# Power_Supply.net
KiCad netlist of a schematic drawn in Altium Designer
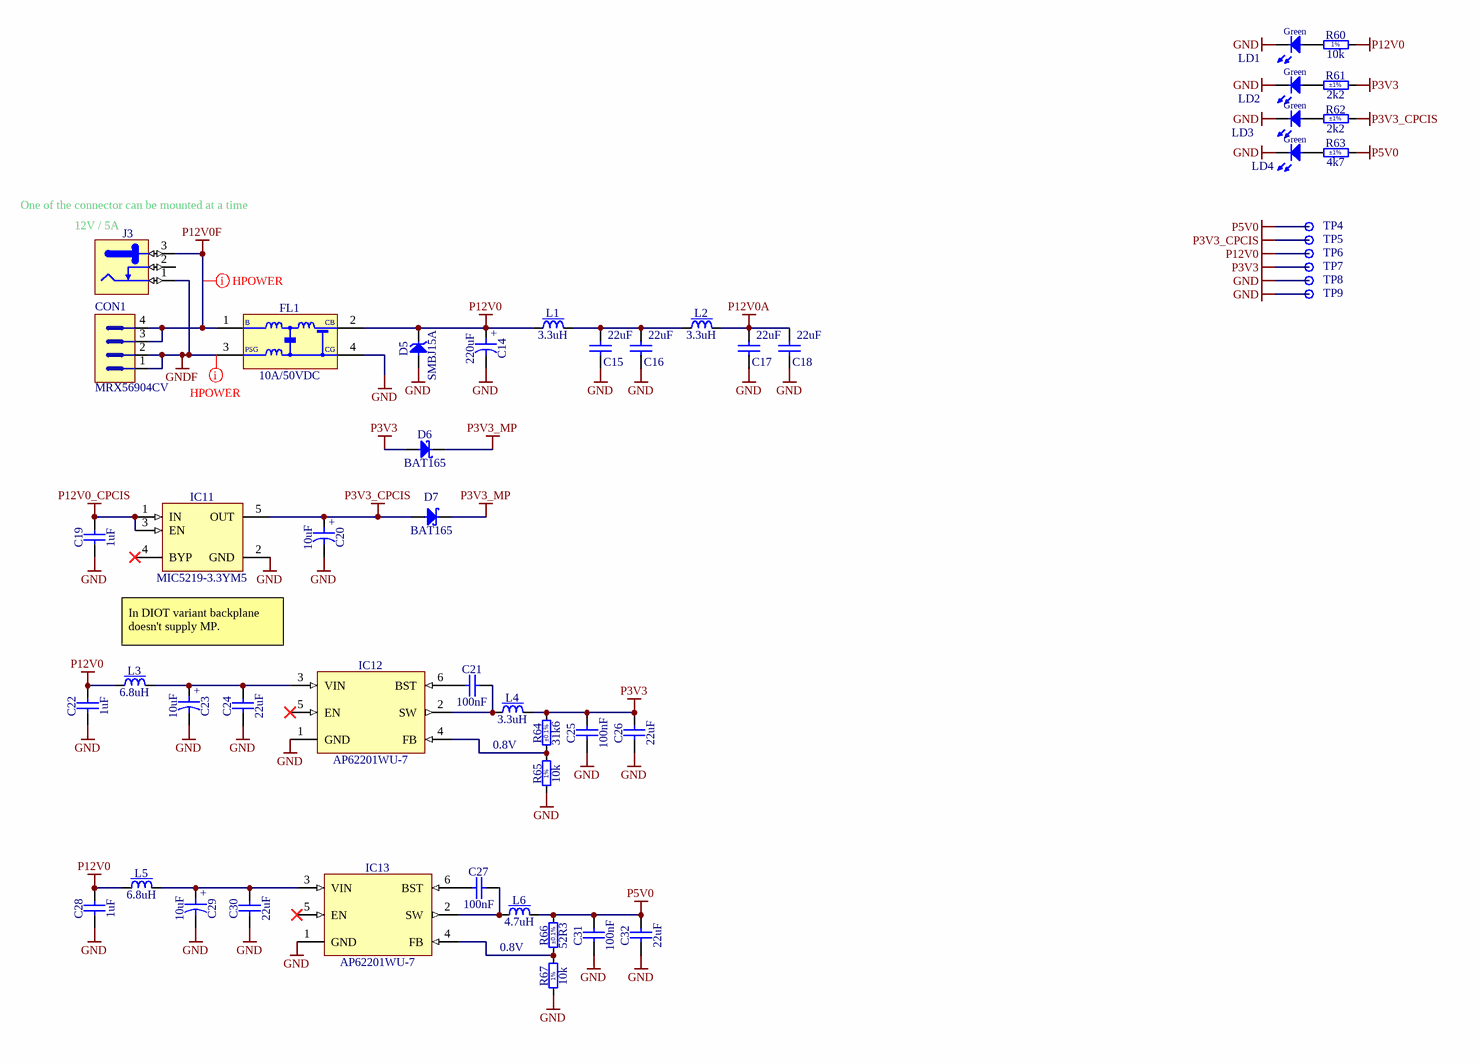
[diagram p0: Power_Supply.SchDoc]

(export (version "E")
  (design (tool "Eeschema 10.0.6"))
  (components
    (comp (ref "C14")
      (value "220uF")
      (footprint "CAPAE830X620N")
      (description "Polarised capacitor")
      (fields
        (field (name "PART NUMBER") "CAE830-620_220UF_16V_20%")
        (field (name "VOLTAGE") "16V")
        (field (name "AUTHOR") "CERN DEM JLC")
      )
      (libsource (lib "Capacitors") (part "Capacitor - polarized"))
    )
    (comp (ref "C15")
      (value "22uF")
      (footprint "CAPC2012X135N")
      (description "Non-polarised capacitor")
      (fields
        (field (name "PART NUMBER") "CC0805_22UF_16V_10%_X5R")
        (field (name "VOLTAGE") "16V")
        (field (name "AUTHOR") "CERN DEM JLC")
      )
      (libsource (lib "Capacitors") (part "Capacitor - non polarized"))
    )
    (comp (ref "C16")
      (value "22uF")
      (footprint "CAPC2012X135N")
      (description "Non-polarised capacitor")
      (fields
        (field (name "PART NUMBER") "CC0805_22UF_16V_10%_X5R")
        (field (name "VOLTAGE") "16V")
        (field (name "AUTHOR") "CERN DEM JLC")
      )
      (libsource (lib "Capacitors") (part "Capacitor - non polarized"))
    )
    (comp (ref "C17")
      (value "22uF")
      (footprint "CAPC2012X135N")
      (description "Non-polarised capacitor")
      (fields
        (field (name "PART NUMBER") "CC0805_22UF_16V_10%_X5R")
        (field (name "VOLTAGE") "16V")
        (field (name "AUTHOR") "CERN DEM JLC")
      )
      (libsource (lib "Capacitors") (part "Capacitor - non polarized"))
    )
    (comp (ref "C18")
      (value "22uF")
      (footprint "CAPC2012X135N")
      (description "Non-polarised capacitor")
      (fields
        (field (name "PART NUMBER") "CC0805_22UF_16V_10%_X5R")
        (field (name "VOLTAGE") "16V")
        (field (name "AUTHOR") "CERN DEM JLC")
      )
      (libsource (lib "Capacitors") (part "Capacitor - non polarized"))
    )
    (comp (ref "C19")
      (value "1uF")
      (footprint "CAPC1608X87N")
      (description "Non-polarised capacitor")
      (fields
        (field (name "PART NUMBER") "CC0603_1UF_25V_10%_X7R")
        (field (name "VOLTAGE") "25V")
        (field (name "AUTHOR") "CERN DEM JLC")
      )
      (libsource (lib "Capacitors") (part "Capacitor - non polarized"))
    )
    (comp (ref "C20")
      (value "10uF")
      (footprint "CAPMP3216X180N")
      (description "Polarised capacitor")
      (fields
        (field (name "PART NUMBER") "CTE3216-18_10UF_16V_20%_AVX_TCJ")
        (field (name "VOLTAGE") "16V")
        (field (name "AUTHOR") "CERN DEM JLC")
      )
      (libsource (lib "Capacitors") (part "Capacitor - polarized"))
    )
    (comp (ref "C21")
      (value "100nF")
      (footprint "CAPC1005X55N")
      (description "Non-polarised capacitor")
      (fields
        (field (name "PART NUMBER") "CC0402_100NF_16V_10%_X5R")
        (field (name "VOLTAGE") "16V")
        (field (name "AUTHOR") "CERN DEM JLC")
      )
      (libsource (lib "Capacitors") (part "Capacitor - non polarized"))
    )
    (comp (ref "C22")
      (value "1uF")
      (footprint "CAPC1608X87N")
      (description "Non-polarised capacitor")
      (fields
        (field (name "PART NUMBER") "CC0603_1UF_25V_10%_X7R")
        (field (name "VOLTAGE") "25V")
        (field (name "AUTHOR") "CERN DEM JLC")
      )
      (libsource (lib "Capacitors") (part "Capacitor - non polarized"))
    )
    (comp (ref "C23")
      (value "10uF")
      (footprint "CAPMP3216X180N")
      (description "Polarised capacitor")
      (fields
        (field (name "PART NUMBER") "CTE3216-18_10UF_16V_20%_AVX_TCJ")
        (field (name "VOLTAGE") "16V")
        (field (name "AUTHOR") "CERN DEM JLC")
      )
      (libsource (lib "Capacitors") (part "Capacitor - polarized"))
    )
    (comp (ref "C24")
      (value "22uF")
      (footprint "CAPC2012X135N")
      (description "Non-polarised capacitor")
      (fields
        (field (name "PART NUMBER") "CC0805_22UF_16V_10%_X5R")
        (field (name "VOLTAGE") "16V")
        (field (name "AUTHOR") "CERN DEM JLC")
      )
      (libsource (lib "Capacitors") (part "Capacitor - non polarized"))
    )
    (comp (ref "C25")
      (value "100nF")
      (footprint "CAPC1005X55N")
      (description "Non-polarised capacitor")
      (fields
        (field (name "PART NUMBER") "CC0402_100NF_16V_10%_X5R")
        (field (name "VOLTAGE") "16V")
        (field (name "AUTHOR") "CERN DEM JLC")
      )
      (libsource (lib "Capacitors") (part "Capacitor - non polarized"))
    )
    (comp (ref "C26")
      (value "22uF")
      (footprint "CAPC2012X135N")
      (description "Non-polarised capacitor")
      (fields
        (field (name "PART NUMBER") "CC0805_22UF_16V_10%_X5R")
        (field (name "VOLTAGE") "16V")
        (field (name "AUTHOR") "CERN DEM JLC")
      )
      (libsource (lib "Capacitors") (part "Capacitor - non polarized"))
    )
    (comp (ref "C27")
      (value "100nF")
      (footprint "CAPC1005X55N")
      (description "Non-polarised capacitor")
      (fields
        (field (name "PART NUMBER") "CC0402_100NF_16V_10%_X5R")
        (field (name "VOLTAGE") "16V")
        (field (name "AUTHOR") "CERN DEM JLC")
      )
      (libsource (lib "Capacitors") (part "Capacitor - non polarized"))
    )
    (comp (ref "C28")
      (value "1uF")
      (footprint "CAPC1608X87N")
      (description "Non-polarised capacitor")
      (fields
        (field (name "PART NUMBER") "CC0603_1UF_25V_10%_X7R")
        (field (name "VOLTAGE") "25V")
        (field (name "AUTHOR") "CERN DEM JLC")
      )
      (libsource (lib "Capacitors") (part "Capacitor - non polarized"))
    )
    (comp (ref "C29")
      (value "10uF")
      (footprint "CAPMP3216X180N")
      (description "Polarised capacitor")
      (fields
        (field (name "PART NUMBER") "CTE3216-18_10UF_16V_20%_AVX_TCJ")
        (field (name "VOLTAGE") "16V")
        (field (name "AUTHOR") "CERN DEM JLC")
      )
      (libsource (lib "Capacitors") (part "Capacitor - polarized"))
    )
    (comp (ref "C30")
      (value "22uF")
      (footprint "CAPC2012X135N")
      (description "Non-polarised capacitor")
      (fields
        (field (name "PART NUMBER") "CC0805_22UF_16V_10%_X5R")
        (field (name "VOLTAGE") "16V")
        (field (name "AUTHOR") "CERN DEM JLC")
      )
      (libsource (lib "Capacitors") (part "Capacitor - non polarized"))
    )
    (comp (ref "C31")
      (value "100nF")
      (footprint "CAPC1005X55N")
      (description "Non-polarised capacitor")
      (fields
        (field (name "PART NUMBER") "CC0402_100NF_16V_10%_X5R")
        (field (name "VOLTAGE") "16V")
        (field (name "AUTHOR") "CERN DEM JLC")
      )
      (libsource (lib "Capacitors") (part "Capacitor - non polarized"))
    )
    (comp (ref "C32")
      (value "22uF")
      (footprint "CAPC2012X135N")
      (description "Non-polarised capacitor")
      (fields
        (field (name "PART NUMBER") "CC0805_22UF_16V_10%_X5R")
        (field (name "VOLTAGE") "16V")
        (field (name "AUTHOR") "CERN DEM JLC")
      )
      (libsource (lib "Capacitors") (part "Capacitor - non polarized"))
    )
    (comp (ref "CON1")
      (value "MRX56904CV")
      (footprint "MRX56904CV")
      (description "4.2mm cripm terminal header")
      (libsource (lib "LIBRARY_SCH") (part "CON_CRIMP_4.2mm_RA_4"))
    )
    (comp (ref "D5")
      (value "SMBJ15A")
      (footprint "DIOM5336X265N")
      (description "Zener Diode")
      (fields
        (field (name "VOLTAGE") "15V")
        (field (name "POWER") "600W")
        (field (name "AUTHOR") "CERN DEM JLC")
      )
      (libsource (lib "ICs And Semiconductors") (part "Diode Zener"))
    )
    (comp (ref "D6")
      (value "BAT165")
      (footprint "SOD2512X110N")
      (description "Schottky Diode")
      (fields
        (field (name "VOLTAGE") "40V")
        (field (name "POWER") "750mA")
        (field (name "AUTHOR") "CERN DEM JLC")
      )
      (libsource (lib "ICs And Semiconductors") (part "Diode Schottky"))
    )
    (comp (ref "D7")
      (value "BAT165")
      (footprint "SOD2512X110N")
      (description "Schottky Diode")
      (fields
        (field (name "MANUFACTURER") "INFINEON")
        (field (name "VOLTAGE") "40V")
        (field (name "AUTHOR") "CERN DEM JLC")
      )
      (libsource (lib "ICs And Semiconductors") (part "Diode Schottky"))
    )
    (comp (ref "FL1")
      (value "10A/50VDC")
      (footprint "FIL_MURATA_BNX02")
      (description "Block Type EMIFIL (LC Combined)")
      (fields
        (field (name "PART NUMBER") "FIL_MURATA_BNX022-01L")
        (field (name "MANUFACTURER") "MURATA")
        (field (name "AUTHOR") "CERN DEM JLC")
      )
      (libsource (lib "Inductors & Transformers") (part "FIL_MURATA_BNX02"))
    )
    (comp (ref "IC11")
      (value "MIC5219-3.3YM5")
      (footprint "SOT95P280X145-5N")
      (description "500mA Peak Output LDO Regulator")
      (fields (field (name "MANUFACTURER") "MICROCHIP TECHNOLOGY") (field (name "AUTHOR") "CERN DEM WB"))
      (libsource (lib "ICs And Semiconductors") (part "MIC5219-X.XYM5"))
    )
    (comp (ref "IC12")
      (value "AP62201WU-7")
      (footprint "SOT95P280X100-6N")
      (description "4.2V TO 18V INPUT, 2A LOW IQ SYNCHRONOUS BUCK CONVERTER")
      (fields (field (name "MANUFACTURER") "DIODES INCORPORATED") (field (name "AUTHOR") "CERN DEM HF"))
      (libsource (lib "ICs And Semiconductors") (part "AP62201WU"))
    )
    (comp (ref "IC13")
      (value "AP62201WU-7")
      (footprint "SOT95P280X100-6N")
      (description "4.2V TO 18V INPUT, 2A LOW IQ SYNCHRONOUS BUCK CONVERTER")
      (fields (field (name "MANUFACTURER") "DIODES INCORPORATED") (field (name "AUTHOR") "CERN DEM HF"))
      (libsource (lib "ICs And Semiconductors") (part "AP62201WU"))
    )
    (comp (ref "J3")
      (value "Jack")
      (footprint "SWITCHCRAFT_L712RA")
      (description "24V /3. 5A, 2.1mm Diameter Pin, SMD DC Power Supply Connector With  Break Contact")
      (fields
        (field (name "PART NUMBER") "SWITCHCRAFT_L712RA")
        (field (name "MANUFACTURER") "SWITCHCRAFT")
        (field (name "AUTHOR") "GK")
      )
      (libsource (lib "LIBRARY_SCH") (part "CON_DC_5A_THT_RA"))
    )
    (comp (ref "L1")
      (value "3.3uH")
      (footprint "IND_WURTH_WE-TPC_4828")
      (description "Inductor With Core")
      (fields
        (field (name "PART NUMBER") "IND_3.3UH_30%_WURTH_WE-TPC_744043003")
        (field (name "POWER") "2.15A")
        (field (name "AUTHOR") "CERN DEM JLC")
      )
      (libsource (lib "Inductors & Transformers") (part "Inductor With Magnetic core"))
    )
    (comp (ref "L2")
      (value "3.3uH")
      (footprint "IND_WURTH_WE-TPC_4828")
      (description "Inductor With Core")
      (fields
        (field (name "PART NUMBER") "IND_3.3UH_30%_WURTH_WE-TPC_744043003")
        (field (name "POWER") "2.15A")
        (field (name "AUTHOR") "CERN DEM JLC")
      )
      (libsource (lib "Inductors & Transformers") (part "Inductor With Magnetic core"))
    )
    (comp (ref "L3")
      (value "6.8uH")
      (footprint "IND_COILCRAFT_XAL4030")
      (description "Inductor With Core")
      (fields
        (field (name "PART NUMBER") "IND_6.8UH_20%_COILCRAFT_XAL4030")
        (field (name "POWER") "3A")
        (field (name "AUTHOR") "CERN DEM MR")
      )
      (libsource (lib "Inductors & Transformers") (part "Inductor With Magnetic core"))
    )
    (comp (ref "L4")
      (value "3.3uH")
      (footprint "IND_WURTH_WE-TPC_4828")
      (description "Inductor With Core")
      (fields
        (field (name "PART NUMBER") "IND_3.3UH_30%_WURTH_WE-TPC_744043003")
        (field (name "POWER") "2.15A")
        (field (name "AUTHOR") "CERN DEM JLC")
      )
      (libsource (lib "Inductors & Transformers") (part "Inductor With Magnetic core"))
    )
    (comp (ref "L5")
      (value "6.8uH")
      (footprint "IND_COILCRAFT_XAL4030")
      (description "Inductor With Core")
      (fields
        (field (name "PART NUMBER") "IND_6.8UH_20%_COILCRAFT_XAL4030")
        (field (name "POWER") "3A")
        (field (name "AUTHOR") "CERN DEM MR")
      )
      (libsource (lib "Inductors & Transformers") (part "Inductor With Magnetic core"))
    )
    (comp (ref "L6")
      (value "4.7uH")
      (footprint "IND_WURTH_WE-SPC-4838")
      (description "Inductor With Core")
      (fields
        (field (name "PART NUMBER") "IND_4.7UH_20%_WURTH_WE-SPC_74408943047")
        (field (name "POWER") "2.2A")
        (field (name "AUTHOR") "CERN DEM JLC")
      )
      (libsource (lib "Inductors & Transformers") (part "Inductor With Magnetic core"))
    )
    (comp (ref "LD1")
      (value "Green")
      (footprint "LED_KINGBRIGHT_KPH-1608CGCK")
      (description "LED Green 1C 2A")
      (fields
        (field (name "PART NUMBER") "LED_KINGBRIGHT_KPH-1608CGCK")
        (field (name "MANUFACTURER") "KINGBRIGHT")
        (field (name "AUTHOR") "CERN DEM JLC")
      )
      (libsource (lib "ICs And Semiconductors") (part "LED Green 1C 2A"))
    )
    (comp (ref "LD2")
      (value "Green")
      (footprint "LED_KINGBRIGHT_KPH-1608CGCK")
      (description "LED Green 1C 2A")
      (fields
        (field (name "PART NUMBER") "LED_KINGBRIGHT_KPH-1608CGCK")
        (field (name "MANUFACTURER") "KINGBRIGHT")
        (field (name "AUTHOR") "CERN DEM JLC")
      )
      (libsource (lib "ICs And Semiconductors") (part "LED Green 1C 2A"))
    )
    (comp (ref "LD3")
      (value "Green")
      (footprint "LED_KINGBRIGHT_KPH-1608CGCK")
      (description "LED Green 1C 2A")
      (fields
        (field (name "PART NUMBER") "LED_KINGBRIGHT_KPH-1608CGCK")
        (field (name "MANUFACTURER") "KINGBRIGHT")
        (field (name "AUTHOR") "CERN DEM JLC")
      )
      (libsource (lib "ICs And Semiconductors") (part "LED Green 1C 2A"))
    )
    (comp (ref "LD4")
      (value "Green")
      (footprint "LED_KINGBRIGHT_KPH-1608CGCK")
      (description "LED Green 1C 2A")
      (fields
        (field (name "PART NUMBER") "LED_KINGBRIGHT_KPH-1608CGCK")
        (field (name "MANUFACTURER") "KINGBRIGHT")
        (field (name "AUTHOR") "CERN DEM JLC")
      )
      (libsource (lib "ICs And Semiconductors") (part "LED Green 1C 2A"))
    )
    (comp (ref "R60")
      (value "10k")
      (footprint "RESC1005X40N")
      (description "Resistor - 1%")
      (fields
        (field (name "PART NUMBER") "R0402_10K_1%_0.0625W_100PPM")
        (field (name "POWER") "0.0625W")
        (field (name "AUTHOR") "CERN DEM JLC")
      )
      (libsource (lib "Resistors") (part "Resistor - 1%"))
    )
    (comp (ref "R61")
      (value "2k2")
      (footprint "RESC1005X40N")
      (description "Resistor - 1%")
      (fields
        (field (name "TOLERANCE") "±1%")
        (field (name "PART NUMBER") "R0402_2K2_1%_0.0625W_100PPM")
        (field (name "POWER") "0.0625W")
        (field (name "AUTHOR") "CERN DEM JLC")
      )
      (libsource (lib "Resistors") (part "Resistor - 1%"))
    )
    (comp (ref "R62")
      (value "2k2")
      (footprint "RESC1005X40N")
      (description "Resistor - 1%")
      (fields
        (field (name "TOLERANCE") "±1%")
        (field (name "PART NUMBER") "R0402_2K2_1%_0.0625W_100PPM")
        (field (name "POWER") "0.0625W")
        (field (name "AUTHOR") "CERN DEM JLC")
      )
      (libsource (lib "Resistors") (part "Resistor - 1%"))
    )
    (comp (ref "R63")
      (value "4k7")
      (footprint "RESC1005X40N")
      (description "Resistor - 1%")
      (fields
        (field (name "TOLERANCE") "±1%")
        (field (name "PART NUMBER") "R0402_4K7_1%_0.0625W_100PPM")
        (field (name "POWER") "0.0625W")
        (field (name "AUTHOR") "CERN DEM JLC")
      )
      (libsource (lib "Resistors") (part "Resistor - 1%"))
    )
    (comp (ref "R64")
      (value "31k6")
      (footprint "RESC1005X35N")
      (description "Resistor - 0.1%")
      (fields
        (field (name "TOLERANCE") "±0.1%")
        (field (name "PART NUMBER") "R0402_31K6_0.1%_0.063W_25PPM_YAGEO_RT")
        (field (name "POWER") "0.063W")
        (field (name "AUTHOR") "CERN DEM BC")
      )
      (libsource (lib "Resistors") (part "Resistor - 0.1%"))
    )
    (comp (ref "R65")
      (value "10k")
      (footprint "RESC1005X40N")
      (description "Resistor - 1%")
      (fields
        (field (name "PART NUMBER") "R0402_10K_1%_0.0625W_100PPM")
        (field (name "POWER") "0.0625W")
        (field (name "AUTHOR") "CERN DEM JLC")
      )
      (libsource (lib "Resistors") (part "Resistor - 1%"))
    )
    (comp (ref "R66")
      (value "52R3")
      (footprint "RESC1608X55N")
      (description "Resistor - 0.1%")
      (fields
        (field (name "TOLERANCE") "±0.1%")
        (field (name "PART NUMBER") "R0603_52R3_0.1%_0.063W_10PPM")
        (field (name "POWER") "0.063W")
        (field (name "AUTHOR") "CERN DEM JLC")
      )
      (libsource (lib "Resistors") (part "Resistor - 0.1%"))
    )
    (comp (ref "R67")
      (value "10k")
      (footprint "RESC1005X40N")
      (description "Resistor - 1%")
      (fields
        (field (name "PART NUMBER") "R0402_10K_1%_0.0625W_100PPM")
        (field (name "POWER") "0.0625W")
        (field (name "AUTHOR") "CERN DEM JLC")
      )
      (libsource (lib "Resistors") (part "Resistor - 1%"))
    )
    (comp (ref "TP4")
      (value "Test Point")
      (footprint "TPS127")
      (fields (field (name "PART NUMBER") "SMD_PAD_1.27X1.27MM") (field (name "AUTHOR") "CERN DEM JLC"))
      (libsource (lib "Eletro-mechanical") (part "Test Point"))
    )
    (comp (ref "TP5")
      (value "Test Point")
      (footprint "TPS127")
      (fields (field (name "PART NUMBER") "SMD_PAD_1.27X1.27MM") (field (name "AUTHOR") "CERN DEM JLC"))
      (libsource (lib "Eletro-mechanical") (part "Test Point"))
    )
    (comp (ref "TP6")
      (value "Test Point")
      (footprint "TPS127")
      (fields (field (name "PART NUMBER") "SMD_PAD_1.27X1.27MM") (field (name "AUTHOR") "CERN DEM JLC"))
      (libsource (lib "Eletro-mechanical") (part "Test Point"))
    )
    (comp (ref "TP7")
      (value "Test Point")
      (footprint "TPS127")
      (fields (field (name "PART NUMBER") "SMD_PAD_1.27X1.27MM") (field (name "AUTHOR") "CERN DEM JLC"))
      (libsource (lib "Eletro-mechanical") (part "Test Point"))
    )
    (comp (ref "TP8")
      (value "Test Point")
      (footprint "TPS127")
      (fields (field (name "PART NUMBER") "SMD_PAD_1.27X1.27MM") (field (name "AUTHOR") "CERN DEM JLC"))
      (libsource (lib "Eletro-mechanical") (part "Test Point"))
    )
    (comp (ref "TP9")
      (value "Test Point")
      (footprint "TPS127")
      (fields (field (name "PART NUMBER") "SMD_PAD_1.27X1.27MM") (field (name "AUTHOR") "CERN DEM JLC"))
      (libsource (lib "Eletro-mechanical") (part "Test Point"))
    )
  )
  (nets
    (net (code "1") (name "GND") (class "Default")
      (node (ref "C14") (pin "2") (pinfunction "2_2") (pintype "passive"))
      (node (ref "C15") (pin "1") (pinfunction "1_1") (pintype "passive"))
      (node (ref "C16") (pin "1") (pinfunction "1_1") (pintype "passive"))
      (node (ref "C17") (pin "1") (pinfunction "1_1") (pintype "passive"))
      (node (ref "C18") (pin "1") (pinfunction "1_1") (pintype "passive"))
      (node (ref "C19") (pin "1") (pinfunction "1_1") (pintype "passive"))
      (node (ref "C20") (pin "2") (pinfunction "2_2") (pintype "passive"))
      (node (ref "C22") (pin "1") (pinfunction "1_1") (pintype "passive"))
      (node (ref "C23") (pin "2") (pinfunction "2_2") (pintype "passive"))
      (node (ref "C24") (pin "1") (pinfunction "1_1") (pintype "passive"))
      (node (ref "C25") (pin "1") (pinfunction "1_1") (pintype "passive"))
      (node (ref "C26") (pin "1") (pinfunction "1_1") (pintype "passive"))
      (node (ref "C28") (pin "1") (pinfunction "1_1") (pintype "passive"))
      (node (ref "C29") (pin "2") (pinfunction "2_2") (pintype "passive"))
      (node (ref "C30") (pin "1") (pinfunction "1_1") (pintype "passive"))
      (node (ref "C31") (pin "1") (pinfunction "1_1") (pintype "passive"))
      (node (ref "C32") (pin "1") (pinfunction "1_1") (pintype "passive"))
      (node (ref "D5") (pin "2") (pinfunction "A_2") (pintype "passive"))
      (node (ref "FL1") (pin "4") (pinfunction "CG_4") (pintype "passive"))
      (node (ref "IC11") (pin "2") (pinfunction "GND_2") (pintype "power_in"))
      (node (ref "IC12") (pin "1") (pinfunction "GND_1") (pintype "power_in"))
      (node (ref "IC13") (pin "1") (pinfunction "GND_1") (pintype "power_in"))
      (node (ref "LD1") (pin "1") (pinfunction "C_1") (pintype "passive"))
      (node (ref "LD2") (pin "1") (pinfunction "C_1") (pintype "passive"))
      (node (ref "LD3") (pin "1") (pinfunction "C_1") (pintype "passive"))
      (node (ref "LD4") (pin "1") (pinfunction "C_1") (pintype "passive"))
      (node (ref "R65") (pin "1") (pinfunction "1_1") (pintype "passive"))
      (node (ref "R67") (pin "1") (pinfunction "1_1") (pintype "passive"))
      (node (ref "TP8") (pin "1") (pinfunction "1_1") (pintype "bidirectional"))
      (node (ref "TP9") (pin "1") (pinfunction "1_1") (pintype "bidirectional"))
    )
    (net (code "2") (name "GNDF") (class "Default")
      (node (ref "CON1") (pin "1") (pinfunction "1_1") (pintype "bidirectional"))
      (node (ref "CON1") (pin "2") (pinfunction "2_2") (pintype "bidirectional"))
      (node (ref "FL1") (pin "3") (pinfunction "PSG_3") (pintype "passive"))
      (node (ref "J3") (pin "1") (pinfunction "1_1") (pintype "bidirectional"))
    )
    (net (code "3") (name "Net-(C15-Pad2)") (class "Default")
      (node (ref "C15") (pin "2") (pinfunction "2_2") (pintype "passive"))
      (node (ref "C16") (pin "2") (pinfunction "2_2") (pintype "passive"))
      (node (ref "L1") (pin "2") (pinfunction "2_2") (pintype "passive"))
      (node (ref "L2") (pin "1") (pinfunction "1_1") (pintype "passive"))
    )
    (net (code "4") (name "Net-(IC12-BST)") (class "Default")
      (node (ref "C21") (pin "1") (pinfunction "1_1") (pintype "passive"))
      (node (ref "IC12") (pin "6") (pinfunction "BST_6") (pintype "input"))
    )
    (net (code "5") (name "Net-(IC12-FB)") (class "Default")
      (node (ref "IC12") (pin "4") (pinfunction "FB_4") (pintype "input"))
      (node (ref "R64") (pin "1") (pinfunction "1_1") (pintype "passive"))
      (node (ref "R65") (pin "2") (pinfunction "2_2") (pintype "passive"))
    )
    (net (code "6") (name "Net-(IC12-SW)") (class "Default")
      (node (ref "C21") (pin "2") (pinfunction "2_2") (pintype "passive"))
      (node (ref "IC12") (pin "2") (pinfunction "SW_2") (pintype "output"))
      (node (ref "L4") (pin "1") (pinfunction "1_1") (pintype "passive"))
    )
    (net (code "7") (name "Net-(IC12-VIN)") (class "Default")
      (node (ref "C23") (pin "1") (pinfunction "1_1") (pintype "passive"))
      (node (ref "C24") (pin "2") (pinfunction "2_2") (pintype "passive"))
      (node (ref "IC12") (pin "3") (pinfunction "VIN_3") (pintype "input"))
      (node (ref "L3") (pin "2") (pinfunction "2_2") (pintype "passive"))
    )
    (net (code "8") (name "Net-(IC13-BST)") (class "Default")
      (node (ref "C27") (pin "1") (pinfunction "1_1") (pintype "passive"))
      (node (ref "IC13") (pin "6") (pinfunction "BST_6") (pintype "input"))
    )
    (net (code "9") (name "Net-(IC13-FB)") (class "Default")
      (node (ref "IC13") (pin "4") (pinfunction "FB_4") (pintype "input"))
      (node (ref "R66") (pin "1") (pinfunction "1_1") (pintype "passive"))
      (node (ref "R67") (pin "2") (pinfunction "2_2") (pintype "passive"))
    )
    (net (code "10") (name "Net-(IC13-SW)") (class "Default")
      (node (ref "C27") (pin "2") (pinfunction "2_2") (pintype "passive"))
      (node (ref "IC13") (pin "2") (pinfunction "SW_2") (pintype "output"))
      (node (ref "L6") (pin "1") (pinfunction "1_1") (pintype "passive"))
    )
    (net (code "11") (name "Net-(IC13-VIN)") (class "Default")
      (node (ref "C29") (pin "1") (pinfunction "1_1") (pintype "passive"))
      (node (ref "C30") (pin "2") (pinfunction "2_2") (pintype "passive"))
      (node (ref "IC13") (pin "3") (pinfunction "VIN_3") (pintype "input"))
      (node (ref "L5") (pin "2") (pinfunction "2_2") (pintype "passive"))
    )
    (net (code "12") (name "Net-(LD1-A)") (class "Default")
      (node (ref "LD1") (pin "2") (pinfunction "A_2") (pintype "passive"))
      (node (ref "R60") (pin "1") (pinfunction "1_1") (pintype "passive"))
    )
    (net (code "13") (name "Net-(LD2-A)") (class "Default")
      (node (ref "LD2") (pin "2") (pinfunction "A_2") (pintype "passive"))
      (node (ref "R61") (pin "1") (pinfunction "1_1") (pintype "passive"))
    )
    (net (code "14") (name "Net-(LD3-A)") (class "Default")
      (node (ref "LD3") (pin "2") (pinfunction "A_2") (pintype "passive"))
      (node (ref "R62") (pin "1") (pinfunction "1_1") (pintype "passive"))
    )
    (net (code "15") (name "Net-(LD4-A)") (class "Default")
      (node (ref "LD4") (pin "2") (pinfunction "A_2") (pintype "passive"))
      (node (ref "R63") (pin "1") (pinfunction "1_1") (pintype "passive"))
    )
    (net (code "16") (name "P3V3") (class "Default")
      (node (ref "C25") (pin "2") (pinfunction "2_2") (pintype "passive"))
      (node (ref "C26") (pin "2") (pinfunction "2_2") (pintype "passive"))
      (node (ref "D6") (pin "2") (pinfunction "A_2") (pintype "passive"))
      (node (ref "L4") (pin "2") (pinfunction "2_2") (pintype "passive"))
      (node (ref "R61") (pin "2") (pinfunction "2_2") (pintype "passive"))
      (node (ref "R64") (pin "2") (pinfunction "2_2") (pintype "passive"))
      (node (ref "TP7") (pin "1") (pinfunction "1_1") (pintype "bidirectional"))
    )
    (net (code "17") (name "P3V3_CPCIS") (class "Default")
      (node (ref "C20") (pin "1") (pinfunction "1_1") (pintype "passive"))
      (node (ref "D7") (pin "2") (pinfunction "A_2") (pintype "passive"))
      (node (ref "IC11") (pin "5") (pinfunction "OUT_5") (pintype "power_in"))
      (node (ref "R62") (pin "2") (pinfunction "2_2") (pintype "passive"))
      (node (ref "TP5") (pin "1") (pinfunction "1_1") (pintype "bidirectional"))
    )
    (net (code "18") (name "P3V3_MP") (class "Default")
      (node (ref "D6") (pin "1") (pinfunction "C_1") (pintype "passive"))
      (node (ref "D7") (pin "1") (pinfunction "C_1") (pintype "passive"))
    )
    (net (code "19") (name "P5V0") (class "Default")
      (node (ref "C31") (pin "2") (pinfunction "2_2") (pintype "passive"))
      (node (ref "C32") (pin "2") (pinfunction "2_2") (pintype "passive"))
      (node (ref "L6") (pin "2") (pinfunction "2_2") (pintype "passive"))
      (node (ref "R63") (pin "2") (pinfunction "2_2") (pintype "passive"))
      (node (ref "R66") (pin "2") (pinfunction "2_2") (pintype "passive"))
      (node (ref "TP4") (pin "1") (pinfunction "1_1") (pintype "bidirectional"))
    )
    (net (code "20") (name "P12V0") (class "Default")
      (node (ref "C14") (pin "1") (pinfunction "1_1") (pintype "passive"))
      (node (ref "C22") (pin "2") (pinfunction "2_2") (pintype "passive"))
      (node (ref "C28") (pin "2") (pinfunction "2_2") (pintype "passive"))
      (node (ref "D5") (pin "1") (pinfunction "C_1") (pintype "passive"))
      (node (ref "FL1") (pin "2") (pinfunction "CB_2") (pintype "passive"))
      (node (ref "L1") (pin "1") (pinfunction "1_1") (pintype "passive"))
      (node (ref "L3") (pin "1") (pinfunction "1_1") (pintype "passive"))
      (node (ref "L5") (pin "1") (pinfunction "1_1") (pintype "passive"))
      (node (ref "R60") (pin "2") (pinfunction "2_2") (pintype "passive"))
      (node (ref "TP6") (pin "1") (pinfunction "1_1") (pintype "bidirectional"))
    )
    (net (code "21") (name "P12V0A") (class "Default")
      (node (ref "C17") (pin "2") (pinfunction "2_2") (pintype "passive"))
      (node (ref "C18") (pin "2") (pinfunction "2_2") (pintype "passive"))
      (node (ref "L2") (pin "2") (pinfunction "2_2") (pintype "passive"))
    )
    (net (code "22") (name "P12V0F") (class "Default")
      (node (ref "CON1") (pin "3") (pinfunction "3_3") (pintype "bidirectional"))
      (node (ref "CON1") (pin "4") (pinfunction "4_4") (pintype "bidirectional"))
      (node (ref "FL1") (pin "1") (pinfunction "B_1") (pintype "passive"))
      (node (ref "J3") (pin "3") (pinfunction "3_3") (pintype "bidirectional"))
    )
    (net (code "23") (name "P12V0_CPCIS") (class "Default")
      (node (ref "C19") (pin "2") (pinfunction "2_2") (pintype "passive"))
      (node (ref "IC11") (pin "1") (pinfunction "IN_1") (pintype "input"))
      (node (ref "IC11") (pin "3") (pinfunction "EN_3") (pintype "input"))
    )
    (net (code "24") (name "unconnected-(IC11-BYP-Pad4)") (class "Default")
      (node (ref "IC11") (pin "4") (pinfunction "BYP_4") (pintype "passive+no_connect"))
    )
    (net (code "25") (name "unconnected-(IC12-EN-Pad5)") (class "Default")
      (node (ref "IC12") (pin "5") (pinfunction "EN_5") (pintype "input+no_connect"))
    )
    (net (code "26") (name "unconnected-(IC13-EN-Pad5)") (class "Default")
      (node (ref "IC13") (pin "5") (pinfunction "EN_5") (pintype "input+no_connect"))
    )
    (net (code "27") (name "unconnected-(J3-Pad2)") (class "Default")
      (node (ref "J3") (pin "2") (pinfunction "2_2") (pintype "bidirectional"))
    )
  )
)
